# vfdhack32db.net
KiCad netlist of a schematic drawn in EAGLE
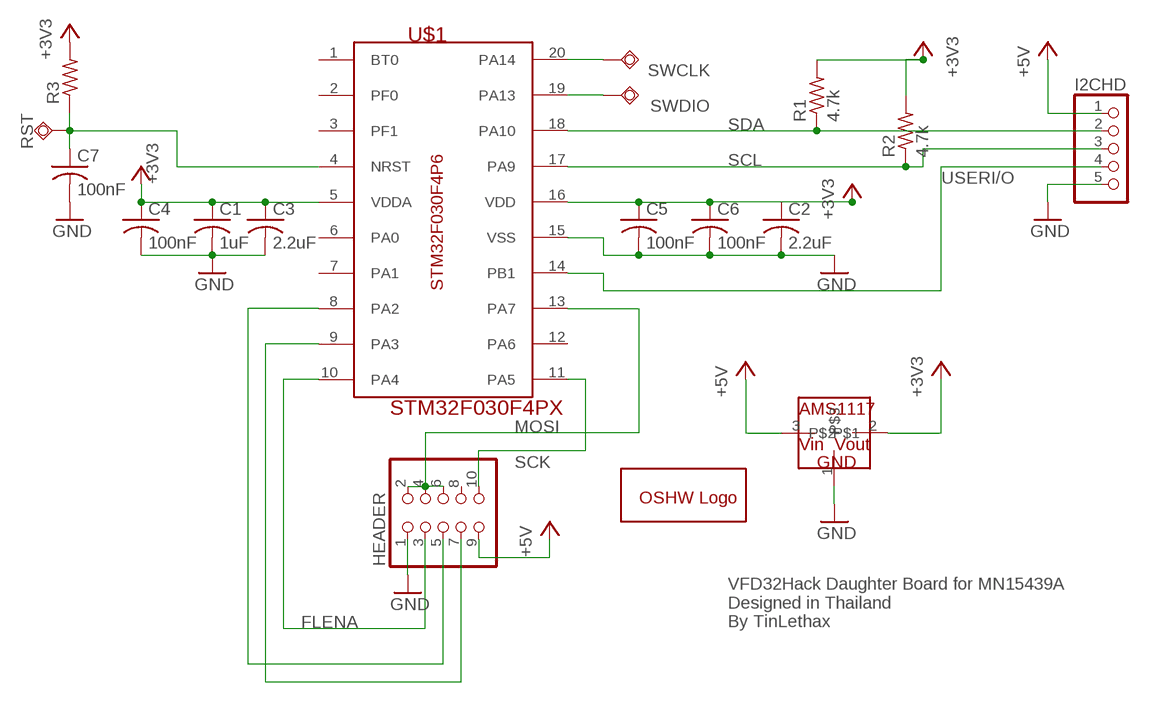
[diagram p0: schematic, sheet 1]

(export (version "E")
  (design (tool "Eeschema 10.0.6"))
  (components
    (comp (ref "C1")
      (value "1uF")
      (footprint "eagle-import:C0603")
      (libsource (lib "eagle-import") (part "C-USC0603"))
    )
    (comp (ref "C2")
      (value "2.2uF")
      (footprint "eagle-import:C0603")
      (libsource (lib "eagle-import") (part "C-USC0603"))
    )
    (comp (ref "C3")
      (value "2.2uF")
      (footprint "eagle-import:C0603")
      (libsource (lib "eagle-import") (part "C-USC0603"))
    )
    (comp (ref "C4")
      (value "100nF")
      (footprint "eagle-import:C1206K")
      (libsource (lib "eagle-import") (part "C-USC1206K"))
    )
    (comp (ref "C5")
      (value "100nF")
      (footprint "eagle-import:C1206K")
      (libsource (lib "eagle-import") (part "C-USC1206K"))
    )
    (comp (ref "C6")
      (value "100nF")
      (footprint "eagle-import:C1206K")
      (libsource (lib "eagle-import") (part "C-USC1206K"))
    )
    (comp (ref "C7")
      (value "100nF")
      (footprint "eagle-import:C1206K")
      (libsource (lib "eagle-import") (part "C-USC1206K"))
    )
    (comp (ref "GOLD_ORB_SM1")
      (value "OSHWLOGOLOGO5MM")
      (footprint "eagle-import:OSHW_5MM")
      (libsource (lib "eagle-import") (part "OSHWLOGOLOGO5MM"))
    )
    (comp (ref "HEADER")
      (value "PINHD-2X5")
      (footprint "eagle-import:2X05")
      (libsource (lib "eagle-import") (part "PINHD-2X5"))
    )
    (comp (ref "I2CHD")
      (value "PINHD-1X5")
      (footprint "eagle-import:1X05")
      (libsource (lib "eagle-import") (part "PINHD-1X5"))
    )
    (comp (ref "R1")
      (value "4.7k")
      (footprint "eagle-import:R0603")
      (libsource (lib "eagle-import") (part "R-US_R0603"))
    )
    (comp (ref "R2")
      (value "4.7k")
      (footprint "eagle-import:R0603")
      (libsource (lib "eagle-import") (part "R-US_R0603"))
    )
    (comp (ref "R3")
      (value "R-US_R0603")
      (footprint "eagle-import:R0603")
      (libsource (lib "eagle-import") (part "R-US_R0603"))
    )
    (comp (ref "RST")
      (value "TPSQTP10SQ")
      (footprint "eagle-import:TP10SQ")
      (libsource (lib "eagle-import") (part "TPSQTP10SQ"))
    )
    (comp (ref "SWCLK")
      (value "TPSQTP10SQ")
      (footprint "eagle-import:TP10SQ")
      (libsource (lib "eagle-import") (part "TPSQTP10SQ"))
    )
    (comp (ref "SWDIO")
      (value "TPSQTP10SQ")
      (footprint "eagle-import:TP10SQ")
      (libsource (lib "eagle-import") (part "TPSQTP10SQ"))
    )
    (comp (ref "U$1")
      (value "STM32F030F4PX")
      (footprint "eagle-import:SOP65P640X120-20N")
      (libsource (lib "eagle-import") (part "STM32F030F4PX"))
    )
    (comp (ref "U$2")
      (value "AMS1117")
      (footprint "eagle-import:SOT223")
      (libsource (lib "eagle-import") (part "AMS1117"))
    )
  )
  (nets
    (net (code "1") (name "+3V3") (class "Default")
      (node (ref "C1") (pin "1") (pinfunction "1_1") (pintype "passive"))
      (node (ref "C2") (pin "1") (pinfunction "1_1") (pintype "passive"))
      (node (ref "C3") (pin "1") (pinfunction "1_1") (pintype "passive"))
      (node (ref "C4") (pin "1") (pinfunction "1_1") (pintype "passive"))
      (node (ref "C5") (pin "1") (pinfunction "1_1") (pintype "passive"))
      (node (ref "C6") (pin "1") (pinfunction "1_1") (pintype "passive"))
      (node (ref "R1") (pin "2") (pinfunction "2_2") (pintype "passive"))
      (node (ref "R2") (pin "2") (pinfunction "2_2") (pintype "passive"))
      (node (ref "R3") (pin "2") (pinfunction "2_2") (pintype "passive"))
      (node (ref "U$1") (pin "16") (pinfunction "VDD_16") (pintype "bidirectional"))
      (node (ref "U$1") (pin "5") (pinfunction "VDDA_5") (pintype "bidirectional"))
      (node (ref "U$2") (pin "2") (pinfunction "P$2_2") (pintype "bidirectional"))
    )
    (net (code "2") (name "+5V") (class "Default")
      (node (ref "HEADER") (pin "9") (pinfunction "9_9") (pintype "passive"))
      (node (ref "I2CHD") (pin "1") (pinfunction "1_1") (pintype "passive"))
      (node (ref "U$2") (pin "3") (pinfunction "P$1_3") (pintype "bidirectional"))
    )
    (net (code "3") (name "/FLENA") (class "Default")
      (node (ref "HEADER") (pin "3") (pinfunction "3_3") (pintype "passive"))
      (node (ref "U$1") (pin "10") (pinfunction "PA4_10") (pintype "bidirectional"))
    )
    (net (code "4") (name "/MOSI") (class "Default")
      (node (ref "HEADER") (pin "2") (pinfunction "2_2") (pintype "passive"))
      (node (ref "HEADER") (pin "4") (pinfunction "4_4") (pintype "passive"))
      (node (ref "HEADER") (pin "6") (pinfunction "6_6") (pintype "passive"))
      (node (ref "U$1") (pin "13") (pinfunction "PA7_13") (pintype "bidirectional"))
    )
    (net (code "5") (name "/SCK") (class "Default")
      (node (ref "HEADER") (pin "10") (pinfunction "10_10") (pintype "passive"))
      (node (ref "U$1") (pin "11") (pinfunction "PA5_11") (pintype "bidirectional"))
    )
    (net (code "6") (name "/SCL") (class "Default")
      (node (ref "I2CHD") (pin "3") (pinfunction "3_3") (pintype "passive"))
      (node (ref "R2") (pin "1") (pinfunction "1_1") (pintype "passive"))
      (node (ref "U$1") (pin "17") (pinfunction "PA9_17") (pintype "bidirectional"))
    )
    (net (code "7") (name "/SDA") (class "Default")
      (node (ref "I2CHD") (pin "2") (pinfunction "2_2") (pintype "passive"))
      (node (ref "R1") (pin "1") (pinfunction "1_1") (pintype "passive"))
      (node (ref "U$1") (pin "18") (pinfunction "PA10_18") (pintype "bidirectional"))
    )
    (net (code "8") (name "/USERI{slash}O") (class "Default")
      (node (ref "I2CHD") (pin "4") (pinfunction "4_4") (pintype "passive"))
      (node (ref "U$1") (pin "14") (pinfunction "PB1_14") (pintype "bidirectional"))
    )
    (net (code "9") (name "GND") (class "Default")
      (node (ref "C1") (pin "2") (pinfunction "2_2") (pintype "passive"))
      (node (ref "C2") (pin "2") (pinfunction "2_2") (pintype "passive"))
      (node (ref "C3") (pin "2") (pinfunction "2_2") (pintype "passive"))
      (node (ref "C4") (pin "2") (pinfunction "2_2") (pintype "passive"))
      (node (ref "C5") (pin "2") (pinfunction "2_2") (pintype "passive"))
      (node (ref "C6") (pin "2") (pinfunction "2_2") (pintype "passive"))
      (node (ref "C7") (pin "2") (pinfunction "2_2") (pintype "passive"))
      (node (ref "HEADER") (pin "1") (pinfunction "1_1") (pintype "passive"))
      (node (ref "I2CHD") (pin "5") (pinfunction "5_5") (pintype "passive"))
      (node (ref "U$1") (pin "15") (pinfunction "VSS_15") (pintype "bidirectional"))
      (node (ref "U$2") (pin "1") (pinfunction "P$3_1") (pintype "bidirectional"))
    )
    (net (code "10") (name "Net-(U$1-NRST)") (class "Default")
      (node (ref "C7") (pin "1") (pinfunction "1_1") (pintype "passive"))
      (node (ref "R3") (pin "1") (pinfunction "1_1") (pintype "passive"))
      (node (ref "RST") (pin "TP") (pinfunction "TP_TP") (pintype "input"))
      (node (ref "U$1") (pin "4") (pinfunction "NRST_4") (pintype "bidirectional"))
    )
    (net (code "11") (name "Net-(U$1-PA2)") (class "Default")
      (node (ref "HEADER") (pin "5") (pinfunction "5_5") (pintype "passive"))
      (node (ref "U$1") (pin "8") (pinfunction "PA2_8") (pintype "bidirectional"))
    )
    (net (code "12") (name "Net-(U$1-PA3)") (class "Default")
      (node (ref "HEADER") (pin "7") (pinfunction "7_7") (pintype "passive"))
      (node (ref "U$1") (pin "9") (pinfunction "PA3_9") (pintype "bidirectional"))
    )
    (net (code "13") (name "Net-(U$1-PA13)") (class "Default")
      (node (ref "SWDIO") (pin "TP") (pinfunction "TP_TP") (pintype "input"))
      (node (ref "U$1") (pin "19") (pinfunction "PA13_19") (pintype "bidirectional"))
    )
    (net (code "14") (name "Net-(U$1-PA14)") (class "Default")
      (node (ref "SWCLK") (pin "TP") (pinfunction "TP_TP") (pintype "input"))
      (node (ref "U$1") (pin "20") (pinfunction "PA14_20") (pintype "bidirectional"))
    )
    (net (code "15") (name "unconnected-(HEADER-Pad8)") (class "Default")
      (node (ref "HEADER") (pin "8") (pinfunction "8_8") (pintype "passive"))
    )
    (net (code "16") (name "unconnected-(U$1-BT0-Pad1)") (class "Default")
      (node (ref "U$1") (pin "1") (pinfunction "BT0_1") (pintype "bidirectional"))
    )
    (net (code "17") (name "unconnected-(U$1-PA0-Pad6)") (class "Default")
      (node (ref "U$1") (pin "6") (pinfunction "PA0_6") (pintype "bidirectional"))
    )
    (net (code "18") (name "unconnected-(U$1-PA1-Pad7)") (class "Default")
      (node (ref "U$1") (pin "7") (pinfunction "PA1_7") (pintype "bidirectional"))
    )
    (net (code "19") (name "unconnected-(U$1-PA6-Pad12)") (class "Default")
      (node (ref "U$1") (pin "12") (pinfunction "PA6_12") (pintype "bidirectional"))
    )
    (net (code "20") (name "unconnected-(U$1-PF0-Pad2)") (class "Default")
      (node (ref "U$1") (pin "2") (pinfunction "PF0_2") (pintype "bidirectional"))
    )
    (net (code "21") (name "unconnected-(U$1-PF1-Pad3)") (class "Default")
      (node (ref "U$1") (pin "3") (pinfunction "PF1_3") (pintype "bidirectional"))
    )
  )
)
